# Gas_Sensor_Schematic.net
KiCad netlist of a schematic drawn in Altium Designer
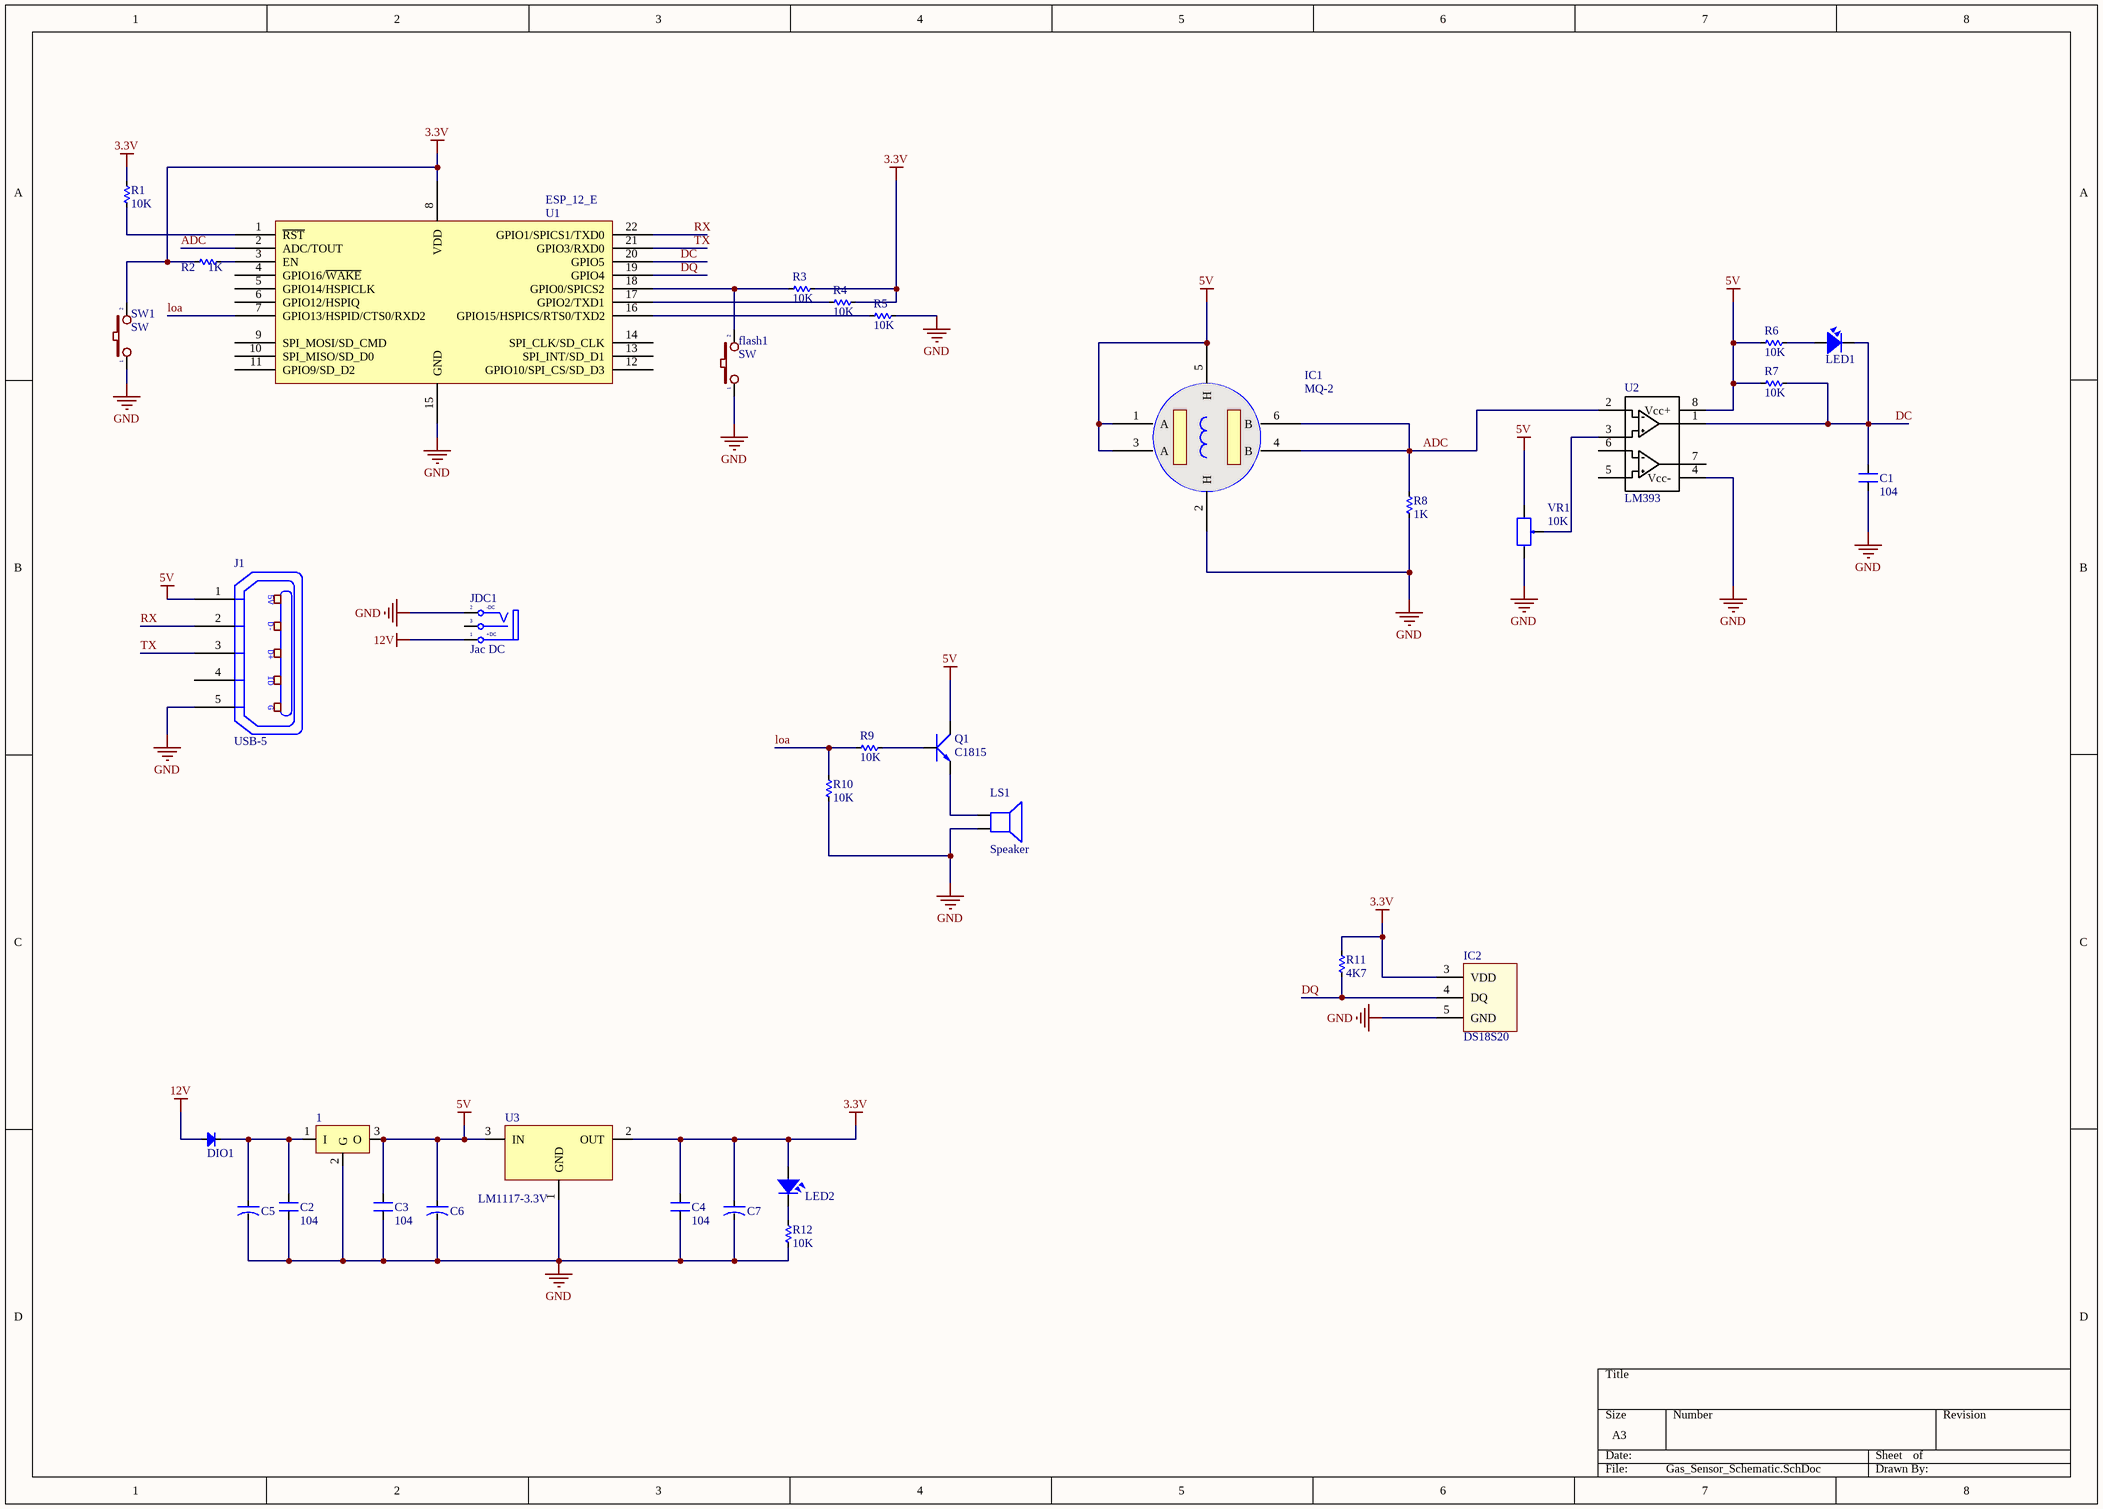
[diagram p0: Gas_Sensor_Schematic.SchDoc]

(export (version "E")
  (design (tool "Eeschema 10.0.6"))
  (components
    (comp (ref "1")
      (value "LM78xx")
      (footprint "TO252-123")
      (description "Positive Voltage Regulator")
      (fields (field (name "PUBLISHER") "Altium Limited"))
      (libsource (lib "LIBRARY") (part "LM78xx"))
    )
    (comp (ref "C1")
      (value "104")
      (footprint "SM-CAP-0805")
      (fields (field (name "DESIGNED BY") "VanDungEvn"))
      (libsource (lib "electronicvn-library1") (part "CN"))
    )
    (comp (ref "C2")
      (value "104")
      (footprint "SM-CAP-0805")
      (fields (field (name "DESIGNED BY") "VanDungEvn"))
      (libsource (lib "electronicvn-library1") (part "CN"))
    )
    (comp (ref "C3")
      (value "104")
      (footprint "SM-CAP-0805")
      (fields (field (name "DESIGNED BY") "VanDungEvn"))
      (libsource (lib "electronicvn-library1") (part "CN"))
    )
    (comp (ref "C4")
      (value "104")
      (footprint "SM-CAP-0805")
      (fields (field (name "DESIGNED BY") "VanDungEvn"))
      (libsource (lib "electronicvn-library1") (part "CN"))
    )
    (comp (ref "C5")
      (value "CN-ALU-SMD")
      (footprint "CAP-ALU-SMD-4.5x5x1.4")
      (description "Polarized Capacitor (Axial)")
      (fields (field (name "PUBLISHER") "Altium Limited"))
      (libsource (lib "LIBTanCN") (part "CN-ALU-SMD"))
    )
    (comp (ref "C6")
      (value "CN-ALU-SMD")
      (footprint "CAP-ALU-SMD-4.5x5x1.4")
      (description "Polarized Capacitor (Axial)")
      (fields (field (name "PUBLISHER") "Altium Limited"))
      (libsource (lib "LIBTanCN") (part "CN-ALU-SMD"))
    )
    (comp (ref "C7")
      (value "CN-ALU-SMD")
      (footprint "CAP-ALU-SMD-4.5x5x1.4")
      (description "Polarized Capacitor (Axial)")
      (fields (field (name "PUBLISHER") "Altium Limited"))
      (libsource (lib "LIBTanCN") (part "CN-ALU-SMD"))
    )
    (comp (ref "DIO1")
      (value "Diode SMD")
      (footprint "DIO-SMD-106")
      (description "Default Diode")
      (fields (field (name "PUBLISHER") "Altium Limited"))
      (libsource (lib "LIBRARY") (part "Diode SMD"))
    )
    (comp (ref "flash1")
      (value "SW")
      (footprint "SW-DIP1")
      (description "Switch button 2 pin")
      (libsource (lib "LIBRARY") (part "SW2"))
    )
    (comp (ref "IC1")
      (value "MQ-2")
      (footprint "heromap:MQ-2")
      (description "MQ-2 GAS SENSOR")
      (libsource (lib "heromap") (part "MQ-2"))
    )
    (comp (ref "IC2")
      (value "DS18S20")
      (footprint "DS18S20")
      (description "High Precision  1-Wire® Digital Thermometer")
      (libsource (lib "LIBTanCN") (part "DS18S20"))
    )
    (comp (ref "J1")
      (value "USB-5")
      (footprint "USB-M1")
      (fields
        (field (name "MANUFACTURER") "FCI")
        (field (name "MANUFACTURER PART NUMBER") "10118193-0001LF")
        (field (name ".CREATOR") "MM")
        (field (name ".CHECKED PCB") "RF")
        (field (name ".CHECKED SCH") "MM")
      )
      (libsource (lib "LIBRARY") (part "USB-5"))
    )
    (comp (ref "JDC1")
      (value "Jac DC")
      (footprint "DC3")
      (description "Jac DC input")
      (libsource (lib "LIBRARY") (part "DCIN"))
    )
    (comp (ref "LED1") (value "LED") (footprint "LED-0805-Blue") (libsource (lib "LIBRARY") (part "LED SMD")))
    (comp (ref "LED2") (value "LED") (footprint "LED-0805-Blue") (libsource (lib "LIBRARY") (part "LED SMD")))
    (comp (ref "LS1")
      (value "Speaker")
      (footprint "SPEAKER")
      (description "Loudspeaker")
      (fields (field (name "PUBLISHER") "Altium Limited"))
      (libsource (lib "LIBRARY") (part "Speaker"))
    )
    (comp (ref "Q1")
      (value "C1815")
      (footprint "SOT23B")
      (description "NPN 600mW, ECB")
      (libsource (lib "electronicvn-library1") (part "C1815"))
    )
    (comp (ref "R1")
      (value "10K")
      (footprint "RES-SMD-0805")
      (description "Resistor")
      (fields
        (field (name "MANUFACTURER") "Generic Components")
        (field (name "PUBLISHER") "Altium Hobart Technology Centre")
      )
      (libsource (lib "LIBRARY") (part "Res-SMD"))
    )
    (comp (ref "R2")
      (value "1K")
      (footprint "RES-SMD-0805")
      (description "Resistor")
      (fields
        (field (name "MANUFACTURER") "Generic Components")
        (field (name "PUBLISHER") "Altium Hobart Technology Centre")
      )
      (libsource (lib "LIBRARY") (part "Res-SMD"))
    )
    (comp (ref "R3")
      (value "10K")
      (footprint "RES-SMD-0805")
      (description "Resistor")
      (fields
        (field (name "MANUFACTURER") "Generic Components")
        (field (name "PUBLISHER") "Altium Hobart Technology Centre")
      )
      (libsource (lib "LIBRARY") (part "Res-SMD"))
    )
    (comp (ref "R4")
      (value "10K")
      (footprint "RES-SMD-0805")
      (description "Resistor")
      (fields
        (field (name "MANUFACTURER") "Generic Components")
        (field (name "PUBLISHER") "Altium Hobart Technology Centre")
      )
      (libsource (lib "LIBRARY") (part "Res-SMD"))
    )
    (comp (ref "R5")
      (value "10K")
      (footprint "RES-SMD-0805")
      (description "Resistor")
      (fields
        (field (name "MANUFACTURER") "Generic Components")
        (field (name "PUBLISHER") "Altium Hobart Technology Centre")
      )
      (libsource (lib "LIBRARY") (part "Res-SMD"))
    )
    (comp (ref "R6")
      (value "10K")
      (footprint "RES-SMD-0805")
      (description "Resistor")
      (fields
        (field (name "MANUFACTURER") "Generic Components")
        (field (name "PUBLISHER") "Altium Hobart Technology Centre")
      )
      (libsource (lib "LIBRARY") (part "Res-SMD"))
    )
    (comp (ref "R7")
      (value "10K")
      (footprint "RES-SMD-0805")
      (description "Resistor")
      (fields
        (field (name "MANUFACTURER") "Generic Components")
        (field (name "PUBLISHER") "Altium Hobart Technology Centre")
      )
      (libsource (lib "LIBRARY") (part "Res-SMD"))
    )
    (comp (ref "R8")
      (value "1K")
      (footprint "RES-SMD-0805")
      (description "Resistor")
      (fields
        (field (name "MANUFACTURER") "Generic Components")
        (field (name "PUBLISHER") "Altium Hobart Technology Centre")
      )
      (libsource (lib "LIBRARY") (part "Res-SMD"))
    )
    (comp (ref "R9")
      (value "10K")
      (footprint "RES-SMD-0805")
      (description "Resistor")
      (fields
        (field (name "MANUFACTURER") "Generic Components")
        (field (name "PUBLISHER") "Altium Hobart Technology Centre")
      )
      (libsource (lib "LIBRARY") (part "Res-SMD"))
    )
    (comp (ref "R10")
      (value "10K")
      (footprint "RES-SMD-0805")
      (description "Resistor")
      (fields
        (field (name "MANUFACTURER") "Generic Components")
        (field (name "PUBLISHER") "Altium Hobart Technology Centre")
      )
      (libsource (lib "LIBRARY") (part "Res-SMD"))
    )
    (comp (ref "R11")
      (value "4K7")
      (footprint "RES-SMD-0805")
      (description "Resistor")
      (fields
        (field (name "MANUFACTURER") "Generic Components")
        (field (name "PUBLISHER") "Altium Hobart Technology Centre")
      )
      (libsource (lib "LIBRARY") (part "Res-SMD"))
    )
    (comp (ref "R12")
      (value "10K")
      (footprint "RES-SMD-0805")
      (description "Resistor")
      (fields
        (field (name "MANUFACTURER") "Generic Components")
        (field (name "PUBLISHER") "Altium Hobart Technology Centre")
      )
      (libsource (lib "LIBRARY") (part "Res-SMD"))
    )
    (comp (ref "SW1")
      (value "SW")
      (footprint "SW1-SMD")
      (description "Switch button 2 pin")
      (libsource (lib "LIBRARY") (part "SW2"))
    )
    (comp (ref "U1")
      (value "ESP_12_E")
      (footprint "ESP_12_E")
      (description "ESP-12 Wi-Fi Module by AI-Thinker")
      (libsource (lib "ESP8266") (part "ESP_12_E"))
    )
    (comp (ref "U2")
      (value "LM393")
      (footprint "SO8")
      (description "IC DUAL COMPARATOR")
      (libsource (lib "LIBRARY") (part "LM393"))
    )
    (comp (ref "U3")
      (value "LM1117-3.3V")
      (footprint "SOT223")
      (description "800mA Low-Dropout Linear Regulator")
      (fields (field (name "CREATOR") "Nguyen Ba Bien"))
      (libsource (lib "LIBRARY") (part "LM1117"))
    )
    (comp (ref "VR1")
      (value "10K")
      (footprint "VR")
      (description "Var Resistor")
      (libsource (lib "LIBTanCN") (part "VR"))
    )
  )
  (nets
    (net (code "1") (name "/ADC") (class "Default")
      (node (ref "IC1") (pin "4") (pinfunction "B_4") (pintype "passive"))
      (node (ref "IC1") (pin "6") (pinfunction "B_6") (pintype "passive"))
      (node (ref "R8") (pin "1") (pinfunction "1_1") (pintype "passive"))
      (node (ref "U1") (pin "2") (pinfunction "ADC/TOUT_2") (pintype "passive"))
      (node (ref "U2") (pin "2") (pintype "passive"))
    )
    (net (code "2") (name "/DC") (class "Default")
      (node (ref "C1") (pin "2") (pinfunction "2_2") (pintype "passive"))
      (node (ref "LED1") (pin "2") (pinfunction "2_2") (pintype "passive"))
      (node (ref "R7") (pin "2") (pinfunction "2_2") (pintype "passive"))
      (node (ref "U1") (pin "20") (pinfunction "GPIO5_20") (pintype "passive"))
      (node (ref "U2") (pin "1") (pintype "passive"))
    )
    (net (code "3") (name "/DQ") (class "Default")
      (node (ref "IC2") (pin "4") (pinfunction "DQ_4") (pintype "passive"))
      (node (ref "R11") (pin "2") (pinfunction "2_2") (pintype "passive"))
      (node (ref "U1") (pin "19") (pinfunction "GPIO4_19") (pintype "passive"))
    )
    (net (code "4") (name "/RX") (class "Default")
      (node (ref "J1") (pin "2") (pinfunction "P2_2") (pintype "passive"))
      (node (ref "U1") (pin "22") (pinfunction "GPIO1/SPICS1/TXD0_22") (pintype "passive"))
    )
    (net (code "5") (name "/TX") (class "Default")
      (node (ref "J1") (pin "3") (pinfunction "P3_3") (pintype "passive"))
      (node (ref "U1") (pin "21") (pinfunction "GPIO3/RXD0_21") (pintype "passive"))
    )
    (net (code "6") (name "/loa") (class "Default")
      (node (ref "R10") (pin "1") (pinfunction "1_1") (pintype "passive"))
      (node (ref "R9") (pin "2") (pinfunction "2_2") (pintype "passive"))
      (node (ref "U1") (pin "7") (pinfunction "GPIO13/HSPID/CTS0/RXD2_7") (pintype "passive"))
    )
    (net (code "7") (name "3.3V") (class "Default")
      (node (ref "C4") (pin "2") (pinfunction "2_2") (pintype "passive"))
      (node (ref "C7") (pin "1") (pinfunction "1_1") (pintype "passive"))
      (node (ref "IC2") (pin "3") (pinfunction "VDD_3") (pintype "passive"))
      (node (ref "LED2") (pin "1") (pinfunction "1_1") (pintype "passive"))
      (node (ref "R1") (pin "1") (pinfunction "1_1") (pintype "passive"))
      (node (ref "R11") (pin "1") (pinfunction "1_1") (pintype "passive"))
      (node (ref "R2") (pin "2") (pinfunction "2_2") (pintype "passive"))
      (node (ref "R3") (pin "1") (pinfunction "1_1") (pintype "passive"))
      (node (ref "R4") (pin "1") (pinfunction "1_1") (pintype "passive"))
      (node (ref "SW1") (pin "2") (pinfunction "2_2") (pintype "passive"))
      (node (ref "U1") (pin "8") (pinfunction "VDD_8") (pintype "passive"))
      (node (ref "U3") (pin "2") (pinfunction "OUT_2") (pintype "passive"))
    )
    (net (code "8") (name "5V") (class "Default")
      (node (ref "1") (pin "3") (pinfunction "O_3") (pintype "power_in"))
      (node (ref "C3") (pin "2") (pinfunction "2_2") (pintype "passive"))
      (node (ref "C6") (pin "1") (pinfunction "1_1") (pintype "passive"))
      (node (ref "IC1") (pin "1") (pinfunction "A_1") (pintype "passive"))
      (node (ref "IC1") (pin "3") (pinfunction "A_3") (pintype "passive"))
      (node (ref "IC1") (pin "5") (pinfunction "H_5") (pintype "passive"))
      (node (ref "J1") (pin "1") (pinfunction "P1_1") (pintype "passive"))
      (node (ref "Q1") (pin "2") (pinfunction "C_2") (pintype "passive"))
      (node (ref "R6") (pin "1") (pinfunction "1_1") (pintype "passive"))
      (node (ref "R7") (pin "1") (pinfunction "1_1") (pintype "passive"))
      (node (ref "U2") (pin "8") (pinfunction "Vcc+_8") (pintype "passive"))
      (node (ref "U3") (pin "3") (pinfunction "IN_3") (pintype "passive"))
      (node (ref "VR1") (pin "1") (pinfunction "1_1") (pintype "passive"))
    )
    (net (code "9") (name "12V") (class "Default")
      (node (ref "DIO1") (pin "1") (pinfunction "A_1") (pintype "passive"))
      (node (ref "JDC1") (pin "1") (pinfunction "T_1") (pintype "passive"))
    )
    (net (code "10") (name "GND") (class "Default")
      (node (ref "1") (pin "2") (pinfunction "G_2") (pintype "power_in"))
      (node (ref "C1") (pin "1") (pinfunction "1_1") (pintype "passive"))
      (node (ref "C2") (pin "1") (pinfunction "1_1") (pintype "passive"))
      (node (ref "C3") (pin "1") (pinfunction "1_1") (pintype "passive"))
      (node (ref "C4") (pin "1") (pinfunction "1_1") (pintype "passive"))
      (node (ref "C5") (pin "2") (pinfunction "2_2") (pintype "passive"))
      (node (ref "C6") (pin "2") (pinfunction "2_2") (pintype "passive"))
      (node (ref "C7") (pin "2") (pinfunction "2_2") (pintype "passive"))
      (node (ref "IC1") (pin "2") (pinfunction "H_2") (pintype "passive"))
      (node (ref "IC2") (pin "5") (pinfunction "GND_5") (pintype "passive"))
      (node (ref "J1") (pin "5") (pinfunction "P5_5") (pintype "passive"))
      (node (ref "JDC1") (pin "2") (pinfunction "TN_2") (pintype "passive"))
      (node (ref "LS1") (pin "2") (pinfunction "2_2") (pintype "passive"))
      (node (ref "R10") (pin "2") (pinfunction "2_2") (pintype "passive"))
      (node (ref "R12") (pin "2") (pinfunction "2_2") (pintype "passive"))
      (node (ref "R5") (pin "1") (pinfunction "1_1") (pintype "passive"))
      (node (ref "R8") (pin "2") (pinfunction "2_2") (pintype "passive"))
      (node (ref "SW1") (pin "1") (pinfunction "1_1") (pintype "passive"))
      (node (ref "U1") (pin "15") (pinfunction "GND_15") (pintype "passive"))
      (node (ref "U2") (pin "4") (pinfunction "Vcc-_4") (pintype "passive"))
      (node (ref "U3") (pin "1") (pinfunction "GND_1") (pintype "passive"))
      (node (ref "VR1") (pin "3") (pinfunction "3_3") (pintype "passive"))
      (node (ref "flash1") (pin "1") (pinfunction "1_1") (pintype "passive"))
    )
    (net (code "11") (name "Net-(1-I)") (class "Default")
      (node (ref "1") (pin "1") (pinfunction "I_1") (pintype "power_in"))
      (node (ref "C2") (pin "2") (pinfunction "2_2") (pintype "passive"))
      (node (ref "C5") (pin "1") (pinfunction "1_1") (pintype "passive"))
      (node (ref "DIO1") (pin "2") (pinfunction "K_2") (pintype "passive"))
    )
    (net (code "12") (name "Net-(LED1-Pad1)") (class "Default")
      (node (ref "LED1") (pin "1") (pinfunction "1_1") (pintype "passive"))
      (node (ref "R6") (pin "2") (pinfunction "2_2") (pintype "passive"))
    )
    (net (code "13") (name "Net-(LED2-Pad2)") (class "Default")
      (node (ref "LED2") (pin "2") (pinfunction "2_2") (pintype "passive"))
      (node (ref "R12") (pin "1") (pinfunction "1_1") (pintype "passive"))
    )
    (net (code "14") (name "Net-(Q1-B)") (class "Default")
      (node (ref "Q1") (pin "3") (pinfunction "B_3") (pintype "passive"))
      (node (ref "R9") (pin "1") (pinfunction "1_1") (pintype "passive"))
    )
    (net (code "15") (name "Net-(Q1-E)") (class "Default")
      (node (ref "LS1") (pin "1") (pinfunction "1_1") (pintype "passive"))
      (node (ref "Q1") (pin "1") (pinfunction "E_1") (pintype "passive"))
    )
    (net (code "16") (name "Net-(U1-EN)") (class "Default")
      (node (ref "R2") (pin "1") (pinfunction "1_1") (pintype "passive"))
      (node (ref "U1") (pin "3") (pinfunction "EN_3") (pintype "passive"))
    )
    (net (code "17") (name "Net-(U1-GPIO0{slash}SPICS2)") (class "Default")
      (node (ref "R3") (pin "2") (pinfunction "2_2") (pintype "passive"))
      (node (ref "U1") (pin "18") (pinfunction "GPIO0/SPICS2_18") (pintype "passive"))
      (node (ref "flash1") (pin "2") (pinfunction "2_2") (pintype "passive"))
    )
    (net (code "18") (name "Net-(U1-GPIO2{slash}TXD1)") (class "Default")
      (node (ref "R4") (pin "2") (pinfunction "2_2") (pintype "passive"))
      (node (ref "U1") (pin "17") (pinfunction "GPIO2/TXD1_17") (pintype "passive"))
    )
    (net (code "19") (name "Net-(U1-GPIO15{slash}HSPICS{slash}RTS0{slash}TXD2)") (class "Default")
      (node (ref "R5") (pin "2") (pinfunction "2_2") (pintype "passive"))
      (node (ref "U1") (pin "16") (pinfunction "GPIO15/HSPICS/RTS0/TXD2_16") (pintype "passive"))
    )
    (net (code "20") (name "Net-(U1-~{RST})") (class "Default")
      (node (ref "R1") (pin "2") (pinfunction "2_2") (pintype "passive"))
      (node (ref "U1") (pin "1") (pinfunction "~{RST}_1") (pintype "passive"))
    )
    (net (code "21") (name "Net-(U2-Pad3)") (class "Default")
      (node (ref "U2") (pin "3") (pintype "passive"))
      (node (ref "VR1") (pin "2") (pinfunction "2_2") (pintype "passive"))
    )
    (net (code "22") (name "unconnected-(J1-P4-Pad4)") (class "Default")
      (node (ref "J1") (pin "4") (pinfunction "P4_4") (pintype "passive"))
    )
    (net (code "23") (name "unconnected-(JDC1-S-Pad3)") (class "Default")
      (node (ref "JDC1") (pin "3") (pinfunction "S_3") (pintype "power_in"))
    )
    (net (code "24") (name "unconnected-(U1-GPIO9{slash}SD_D2-Pad11)") (class "Default")
      (node (ref "U1") (pin "11") (pinfunction "GPIO9/SD_D2_11") (pintype "passive"))
    )
    (net (code "25") (name "unconnected-(U1-GPIO10{slash}SPI_CS{slash}SD_D3-Pad12)") (class "Default")
      (node (ref "U1") (pin "12") (pinfunction "GPIO10/SPI_CS/SD_D3_12") (pintype "passive"))
    )
    (net (code "26") (name "unconnected-(U1-GPIO12{slash}HSPIQ-Pad6)") (class "Default")
      (node (ref "U1") (pin "6") (pinfunction "GPIO12/HSPIQ_6") (pintype "passive"))
    )
    (net (code "27") (name "unconnected-(U1-GPIO14{slash}HSPICLK-Pad5)") (class "Default")
      (node (ref "U1") (pin "5") (pinfunction "GPIO14/HSPICLK_5") (pintype "passive"))
    )
    (net (code "28") (name "unconnected-(U1-GPIO16{slash}~{WAKE}-Pad4)") (class "Default")
      (node (ref "U1") (pin "4") (pinfunction "GPIO16/~{WAKE}_4") (pintype "passive"))
    )
    (net (code "29") (name "unconnected-(U1-SPI_CLK{slash}SD_CLK-Pad14)") (class "Default")
      (node (ref "U1") (pin "14") (pinfunction "SPI_CLK/SD_CLK_14") (pintype "passive"))
    )
    (net (code "30") (name "unconnected-(U1-SPI_INT{slash}SD_D1-Pad13)") (class "Default")
      (node (ref "U1") (pin "13") (pinfunction "SPI_INT/SD_D1_13") (pintype "passive"))
    )
    (net (code "31") (name "unconnected-(U1-SPI_MISO{slash}SD_D0-Pad10)") (class "Default")
      (node (ref "U1") (pin "10") (pinfunction "SPI_MISO/SD_D0_10") (pintype "passive"))
    )
    (net (code "32") (name "unconnected-(U1-SPI_MOSI{slash}SD_CMD-Pad9)") (class "Default")
      (node (ref "U1") (pin "9") (pinfunction "SPI_MOSI/SD_CMD_9") (pintype "passive"))
    )
    (net (code "33") (name "unconnected-(U2-Pad5)") (class "Default")
      (node (ref "U2") (pin "5") (pintype "passive"))
    )
    (net (code "34") (name "unconnected-(U2-Pad6)") (class "Default")
      (node (ref "U2") (pin "6") (pintype "passive"))
    )
    (net (code "35") (name "unconnected-(U2-Pad7)") (class "Default")
      (node (ref "U2") (pin "7") (pintype "passive"))
    )
  )
)
